# High_Voltage_Converter.net
KiCad netlist of a schematic drawn in Altium Designer
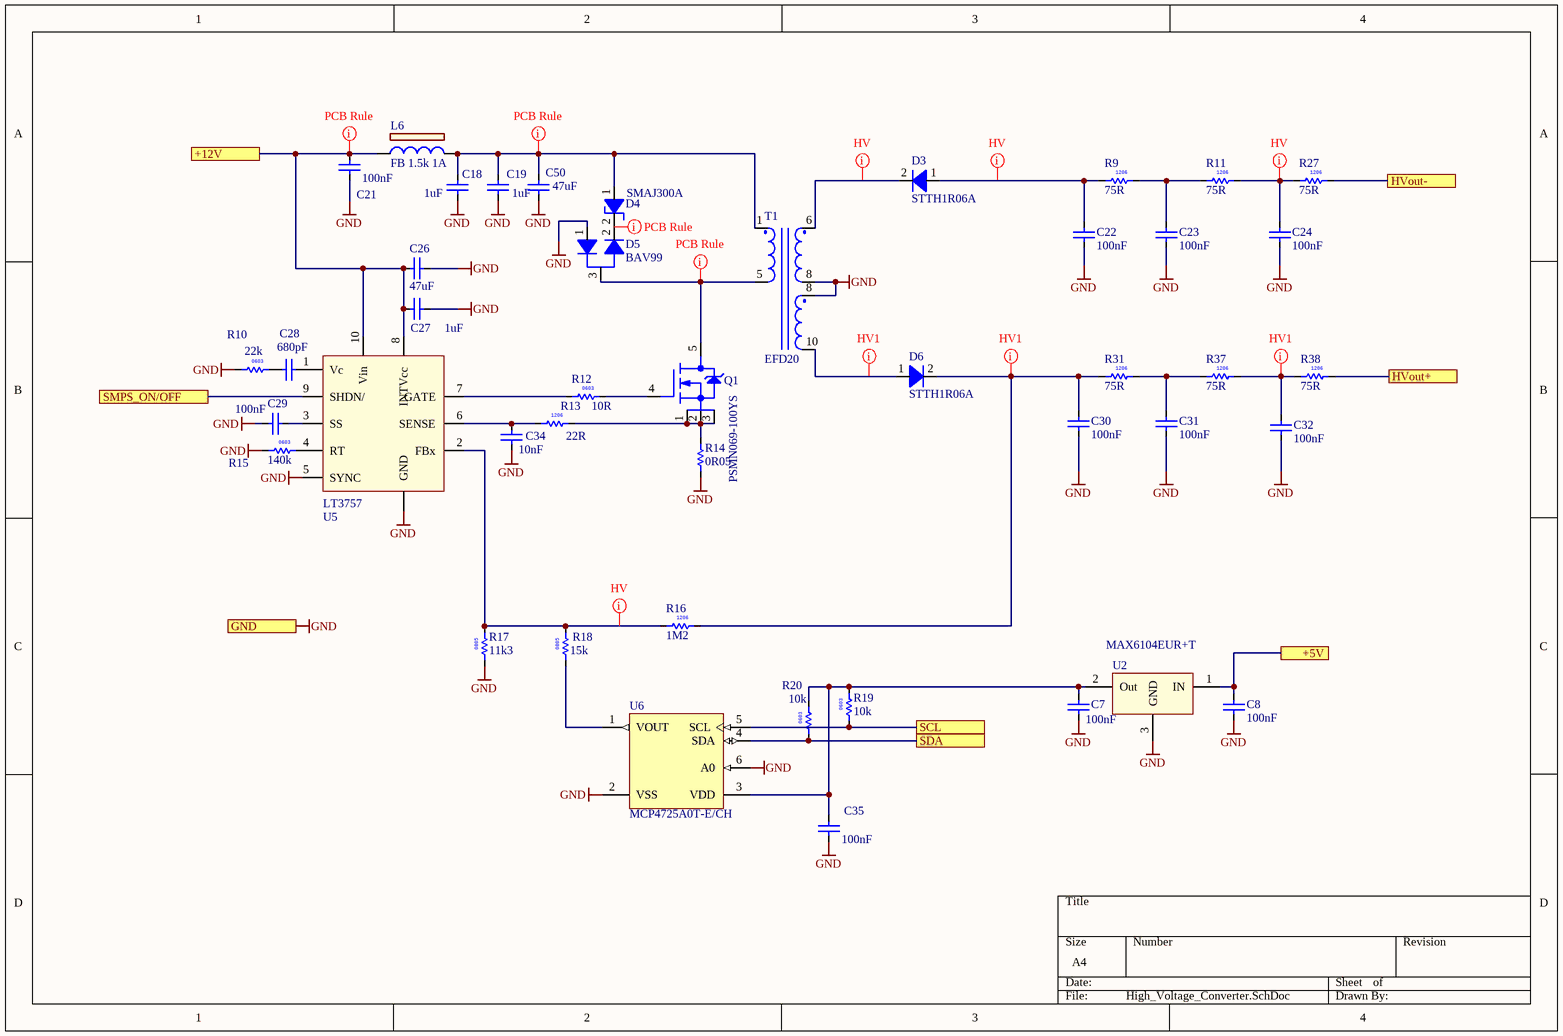
[diagram p0: High_Voltage_Converter.SchDoc]

(export (version "E")
  (design (tool "Eeschema 10.0.6"))
  (components
    (comp (ref "C7")
      (value "100nF")
      (footprint "C0603V")
      (description "MLCC, 0.1uF 16V 10% X7R 0603")
      (fields (field (name "PART NUMBER") "C0000005") (field (name "VOLTAGE") "16"))
      (libsource (lib "KTU_DB") (part "C_SM"))
    )
    (comp (ref "C8")
      (value "100nF")
      (footprint "C0603V")
      (description "MLCC, 0.1uF 16V 10% X7R 0603")
      (fields (field (name "PART NUMBER") "C0000005") (field (name "VOLTAGE") "16"))
      (libsource (lib "KTU_DB") (part "C_SM"))
    )
    (comp (ref "C18")
      (value "1uF")
      (footprint "CAPC2012N")
      (description "MLCC, 0805, X5R, 16V, 1UF")
      (fields (field (name "PART NUMBER") "C0000037") (field (name "VOLTAGE") "16"))
      (libsource (lib "KTU_DB") (part "C_SM"))
    )
    (comp (ref "C19")
      (value "1uF")
      (footprint "CAPC2012N")
      (description "MLCC, 0805, X5R, 16V, 1UF")
      (fields (field (name "PART NUMBER") "C0000037") (field (name "VOLTAGE") "16"))
      (libsource (lib "KTU_DB") (part "C_SM"))
    )
    (comp (ref "C21")
      (value "100nF")
      (footprint "C0603V")
      (description "MLCC, 0.1uF 16V 10% X7R 0603")
      (fields (field (name "PART NUMBER") "C0000005") (field (name "VOLTAGE") "16"))
      (libsource (lib "KTU_DB") (part "C_SM"))
    )
    (comp (ref "C22")
      (value "100nF")
      (footprint "C1808")
      (description "MLCC, X7R, 100NF, 630V, 1808")
      (fields (field (name "PART NUMBER") "C0000111") (field (name "VOLTAGE") "630"))
      (libsource (lib "KTU_DB") (part "C_SM"))
    )
    (comp (ref "C23")
      (value "100nF")
      (footprint "C1808")
      (description "MLCC, X7R, 100NF, 630V, 1808")
      (fields (field (name "PART NUMBER") "C0000111") (field (name "VOLTAGE") "630"))
      (libsource (lib "KTU_DB") (part "C_SM"))
    )
    (comp (ref "C24")
      (value "100nF")
      (footprint "C1808")
      (description "MLCC, X7R, 100NF, 630V, 1808")
      (fields (field (name "PART NUMBER") "C0000111") (field (name "VOLTAGE") "630"))
      (libsource (lib "KTU_DB") (part "C_SM"))
    )
    (comp (ref "C26")
      (value "47uF")
      (footprint "CAPC3225N")
      (description "MLCC, 1210, 47uF, 16V")
      (fields (field (name "PART NUMBER") "C0000077") (field (name "VOLTAGE") "16"))
      (libsource (lib "KTU_DB") (part "C_SM"))
    )
    (comp (ref "C27")
      (value "1uF")
      (footprint "CAPC2012N")
      (description "MLCC, 0805, X5R, 16V, 1UF")
      (fields (field (name "PART NUMBER") "C0000037") (field (name "VOLTAGE") "16"))
      (libsource (lib "KTU_DB") (part "C_SM"))
    )
    (comp (ref "C28")
      (value "680pF")
      (footprint "CAPC3216N")
      (description "MLCC, 680PF, 630V, C0G/NP0, 1206")
      (fields (field (name "PART NUMBER") "C0000056") (field (name "VOLTAGE") "630"))
      (libsource (lib "KTU_DB") (part "C_SM"))
    )
    (comp (ref "C29")
      (value "100nF")
      (footprint "C0603V")
      (description "MLCC, 0.1uF 16V 10% X7R 0603")
      (fields (field (name "PART NUMBER") "C0000005") (field (name "VOLTAGE") "16"))
      (libsource (lib "KTU_DB") (part "C_SM"))
    )
    (comp (ref "C30")
      (value "100nF")
      (footprint "C1808")
      (description "MLCC, X7R, 100NF, 630V, 1808")
      (fields (field (name "PART NUMBER") "C0000111") (field (name "VOLTAGE") "630"))
      (libsource (lib "KTU_DB") (part "C_SM"))
    )
    (comp (ref "C31")
      (value "100nF")
      (footprint "C1808")
      (description "MLCC, X7R, 100NF, 630V, 1808")
      (fields (field (name "PART NUMBER") "C0000111") (field (name "VOLTAGE") "630"))
      (libsource (lib "KTU_DB") (part "C_SM"))
    )
    (comp (ref "C32")
      (value "100nF")
      (footprint "C1808")
      (description "MLCC, X7R, 100NF, 630V, 1808")
      (fields (field (name "PART NUMBER") "C0000111") (field (name "VOLTAGE") "630"))
      (libsource (lib "KTU_DB") (part "C_SM"))
    )
    (comp (ref "C34")
      (value "10nF")
      (footprint "CAPC3216N")
      (description "MLCC, 10nF, 630V, ±10% ,X7R, 1206")
      (fields (field (name "PART NUMBER") "C0000012") (field (name "VOLTAGE") "630"))
      (libsource (lib "KTU_DB") (part "C_SM"))
    )
    (comp (ref "C35")
      (value "100nF")
      (footprint "C0603V")
      (description "MLCC, 0.1uF 16V 10% X7R 0603")
      (fields (field (name "PART NUMBER") "C0000005") (field (name "VOLTAGE") "16"))
      (libsource (lib "KTU_DB") (part "C_SM"))
    )
    (comp (ref "C50")
      (value "47uF")
      (footprint "CAPC3225N")
      (description "MLCC, 1210, 47uF, 16V")
      (fields (field (name "PART NUMBER") "C0000077") (field (name "VOLTAGE") "16"))
      (libsource (lib "KTU_DB") (part "C_SM"))
    )
    (comp (ref "D3")
      (value "STTH1R06A")
      (footprint "DO-214AC")
      (description "DIODE, fast, 1A, 600V, SMD, SMA")
      (fields (field (name "PART NUMBER") "D0000024") (field (name "MANUFACTURER") "ST Microelectronics"))
      (libsource (lib "KTU_DB") (part "Diode"))
    )
    (comp (ref "D4")
      (value "SMAJ300A")
      (footprint "DO-214AC")
      (description "TVS DIODE, 400W, 300V, DO-214AC")
      (fields (field (name "PART NUMBER") "D0000021") (field (name "MANUFACTURER") "LITTELFUSE"))
      (libsource (lib "KTU_DB") (part "Diode_transzorb"))
    )
    (comp (ref "D5")
      (value "BAV99")
      (footprint "SOT95P240-3L")
      (description "DIODE SW DUAL 75V 350mW SOT23")
      (fields (field (name "PART NUMBER") "D0000001") (field (name "MANUFACTURER PART NUMBER") "BAV99-7-F"))
      (libsource (lib "KTU_DB") (part "BAV99"))
    )
    (comp (ref "D6")
      (value "STTH1R06A")
      (footprint "DO-214AC")
      (description "DIODE, fast, 1A, 600V, SMD, SMA")
      (fields (field (name "PART NUMBER") "D0000024") (field (name "MANUFACTURER") "ST Microelectronics"))
      (libsource (lib "KTU_DB") (part "Diode"))
    )
    (comp (ref "L6")
      (value "FB 1.5k 1A")
      (footprint "LL0805\\2P")
      (description "BEAD FERRITE, SMD 1500OHM, 0805")
      (fields (field (name "PART NUMBER") "L0000004") (field (name "MANUFACTURER") "Wurth Elektronik"))
      (libsource (lib "KTU_DB") (part "L_core"))
    )
    (comp (ref "Q1")
      (value "PSMN069-100YS")
      (footprint "SOT669")
      (description "MOSFET 100V, 72.4 mOhm standard level, LFPAK")
      (fields (field (name "PART NUMBER") "Q0000050") (field (name "MANUFACTURER") "NXP"))
      (libsource (lib "KTU_DB") (part "MOSFET_N_GDSSS"))
    )
    (comp (ref "R9")
      (value "75R")
      (footprint "RESC3216N")
      (description "75R 5% 1206 1/4W")
      (fields (field (name "TOLERANCE") "±5%") (field (name "POWER") "1/4W"))
      (libsource (lib "KTU_DB") (part "R1206"))
    )
    (comp (ref "R10")
      (value "22k")
      (footprint "RESC1608X50N")
      (description "Res, 22K, 0603 (1608 metric), ±1%, 100mW, 75V")
      (fields (field (name "TOLERANCE") "±1%") (field (name "POWER") "100mW"))
      (libsource (lib "KTU_DB") (part "R0603"))
    )
    (comp (ref "R11")
      (value "75R")
      (footprint "RESC3216N")
      (description "75R 5% 1206 1/4W")
      (fields (field (name "TOLERANCE") "±5%") (field (name "POWER") "1/4W"))
      (libsource (lib "KTU_DB") (part "R1206"))
    )
    (comp (ref "R12")
      (value "10R")
      (footprint "RESC1608N")
      (description "Res, 0603 0.1W 5%")
      (fields (field (name "TOLERANCE") "±5%") (field (name "POWER") "0.1W"))
      (libsource (lib "KTU_DB") (part "R0603"))
    )
    (comp (ref "R13")
      (value "22R")
      (footprint "RESC3216N")
      (description "22R 5% 1206 1/4W")
      (fields (field (name "TOLERANCE") "±5%") (field (name "POWER") "1/4W"))
      (libsource (lib "KTU_DB") (part "R1206"))
    )
    (comp (ref "R14")
      (value "0R05")
      (footprint "RESC6432AN")
      (description "Res, 0.05R 1% 2512 1W")
      (fields (field (name "TOLERANCE") "±1%") (field (name "POWER") "1W"))
      (libsource (lib "KTU_DB") (part "Res"))
    )
    (comp (ref "R15")
      (value "140k")
      (footprint "RESC1608X50N")
      (description "Res, 140K, 0603 (1608 metric), ±1%, 100mW, 75V")
      (fields (field (name "TOLERANCE") "±1%") (field (name "POWER") "100mW"))
      (libsource (lib "KTU_DB") (part "R0603"))
    )
    (comp (ref "R16")
      (value "1M2")
      (footprint "RESC3216N")
      (description "Res, 1M 0.25W, 1% 1206")
      (fields (field (name "TOLERANCE") "±1%") (field (name "POWER") "0.25W"))
      (libsource (lib "KTU_DB") (part "R1206"))
    )
    (comp (ref "R17")
      (value "11k3")
      (footprint "RESC2012N")
      (description "Res, 11K 5% 0805 1/8W")
      (fields (field (name "TOLERANCE") "±5%") (field (name "POWER") "1/8W"))
      (libsource (lib "KTU_DB") (part "R0805"))
    )
    (comp (ref "R18")
      (value "15k")
      (footprint "RESC2012N")
      (description "Res, 11K 5% 0805 1/8W")
      (fields (field (name "TOLERANCE") "±5%") (field (name "POWER") "1/8W"))
      (libsource (lib "KTU_DB") (part "R0805"))
    )
    (comp (ref "R19")
      (value "10k")
      (footprint "RESC1608N")
      (description "Res, 10K 0.063W 75V 1%  0603")
      (fields (field (name "TOLERANCE") "±1%") (field (name "POWER") "0.063W"))
      (libsource (lib "KTU_DB") (part "R0603"))
    )
    (comp (ref "R20")
      (value "10k")
      (footprint "RESC1608N")
      (description "Res, 10K 0.063W 75V 1%  0603")
      (fields (field (name "TOLERANCE") "±1%") (field (name "POWER") "0.063W"))
      (libsource (lib "KTU_DB") (part "R0603"))
    )
    (comp (ref "R27")
      (value "75R")
      (footprint "RESC3216N")
      (description "75R 5% 1206 1/4W")
      (fields (field (name "TOLERANCE") "±5%") (field (name "POWER") "1/4W"))
      (libsource (lib "KTU_DB") (part "R1206"))
    )
    (comp (ref "R31")
      (value "75R")
      (footprint "RESC3216N")
      (description "75R 5% 1206 1/4W")
      (fields (field (name "TOLERANCE") "±5%") (field (name "POWER") "1/4W"))
      (libsource (lib "KTU_DB") (part "R1206"))
    )
    (comp (ref "R37")
      (value "75R")
      (footprint "RESC3216N")
      (description "75R 5% 1206 1/4W")
      (fields (field (name "TOLERANCE") "±5%") (field (name "POWER") "1/4W"))
      (libsource (lib "KTU_DB") (part "R1206"))
    )
    (comp (ref "R38")
      (value "75R")
      (footprint "RESC3216N")
      (description "75R 5% 1206 1/4W")
      (fields (field (name "TOLERANCE") "±5%") (field (name "POWER") "1/4W"))
      (libsource (lib "KTU_DB") (part "R1206"))
    )
    (comp (ref "T1")
      (value "EFD20")
      (footprint "EFD_20")
      (description "EFD_20")
      (libsource (lib "D_klase") (part "EFD_20"))
    )
    (comp (ref "U2")
      (value "MAX6104EUR+T")
      (footprint "SOT23-3")
      (description "Low-Cost, Micropower, Low-Dropout,  High-Output-Current, SOT23 Voltage References")
      (libsource (lib "D_klase") (part "MAX6104EUR+T"))
    )
    (comp (ref "U5")
      (value "LT3757")
      (footprint "10-LEAD PLASTIC MSOP - duplicate")
      (description "Boost, Flyback, SEPIC and  Inverting Controller")
      (libsource (lib "D_klase") (part "LT3757"))
    )
    (comp (ref "U6")
      (value "MCP4725A0T-E/CH")
      (footprint "SOT-23-CH6_N")
      (fields (field (name "PUBLISHER") "Altium Limited"))
      (libsource (lib "Microchip Mixed Signal") (part "MCP4725A0T-E/CH"))
    )
  )
  (nets
    (net (code "1") (name "/+5V") (class "Default")
      (node (ref "C8") (pin "2") (pinfunction "2_2") (pintype "passive"))
      (node (ref "U2") (pin "1") (pinfunction "IN_1") (pintype "passive"))
    )
    (net (code "2") (name "/+12V") (class "Default")
      (node (ref "C21") (pin "2") (pinfunction "2_2") (pintype "passive"))
      (node (ref "C26") (pin "1") (pinfunction "1_1") (pintype "passive"))
      (node (ref "C27") (pin "1") (pinfunction "1_1") (pintype "passive"))
      (node (ref "L6") (pin "1") (pinfunction "1_1") (pintype "passive"))
      (node (ref "U5") (pin "10") (pinfunction "Vin_10") (pintype "passive"))
      (node (ref "U5") (pin "8") (pinfunction "INTVcc_8") (pintype "passive"))
    )
    (net (code "3") (name "/HVout+") (class "Default")
      (node (ref "R38") (pin "2") (pinfunction "2_2") (pintype "passive"))
    )
    (net (code "4") (name "/HVout-") (class "Default")
      (node (ref "R27") (pin "2") (pinfunction "2_2") (pintype "passive"))
    )
    (net (code "5") (name "/SCL") (class "Default")
      (node (ref "R19") (pin "1") (pinfunction "1_1") (pintype "passive"))
      (node (ref "U6") (pin "5") (pinfunction "SCL_5") (pintype "input"))
    )
    (net (code "6") (name "/SDA") (class "Default")
      (node (ref "R20") (pin "1") (pinfunction "1_1") (pintype "passive"))
      (node (ref "U6") (pin "4") (pinfunction "SDA_4") (pintype "bidirectional"))
    )
    (net (code "7") (name "/SMPS_ON{slash}OFF") (class "Default")
      (node (ref "U5") (pin "9") (pinfunction "SHDN/_9") (pintype "passive"))
    )
    (net (code "8") (name "GND") (class "Default")
      (node (ref "C18") (pin "2") (pinfunction "2_2") (pintype "passive"))
      (node (ref "C19") (pin "2") (pinfunction "2_2") (pintype "passive"))
      (node (ref "C21") (pin "1") (pinfunction "1_1") (pintype "passive"))
      (node (ref "C22") (pin "1") (pinfunction "1_1") (pintype "passive"))
      (node (ref "C23") (pin "1") (pinfunction "1_1") (pintype "passive"))
      (node (ref "C24") (pin "1") (pinfunction "1_1") (pintype "passive"))
      (node (ref "C26") (pin "2") (pinfunction "2_2") (pintype "passive"))
      (node (ref "C27") (pin "2") (pinfunction "2_2") (pintype "passive"))
      (node (ref "C29") (pin "2") (pinfunction "2_2") (pintype "passive"))
      (node (ref "C30") (pin "1") (pinfunction "1_1") (pintype "passive"))
      (node (ref "C31") (pin "1") (pinfunction "1_1") (pintype "passive"))
      (node (ref "C32") (pin "1") (pinfunction "1_1") (pintype "passive"))
      (node (ref "C34") (pin "1") (pinfunction "1_1") (pintype "passive"))
      (node (ref "C35") (pin "1") (pinfunction "1_1") (pintype "passive"))
      (node (ref "C50") (pin "1") (pinfunction "1_1") (pintype "passive"))
      (node (ref "C7") (pin "1") (pinfunction "1_1") (pintype "passive"))
      (node (ref "C8") (pin "1") (pinfunction "1_1") (pintype "passive"))
      (node (ref "D5") (pin "1") (pinfunction "A1_1") (pintype "passive"))
      (node (ref "R10") (pin "1") (pinfunction "1_1") (pintype "passive"))
      (node (ref "R14") (pin "1") (pinfunction "1_1") (pintype "passive"))
      (node (ref "R15") (pin "1") (pinfunction "1_1") (pintype "passive"))
      (node (ref "R17") (pin "1") (pinfunction "1_1") (pintype "passive"))
      (node (ref "T1") (pin "8") (pinfunction "8_8") (pintype "passive"))
      (node (ref "U2") (pin "3") (pinfunction "GND_3") (pintype "passive"))
      (node (ref "U5") (pin "5") (pinfunction "SYNC_5") (pintype "passive"))
      (node (ref "U5") (pin "GND") (pinfunction "GND_GND") (pintype "passive"))
      (node (ref "U6") (pin "2") (pinfunction "VSS_2") (pintype "power_in"))
      (node (ref "U6") (pin "6") (pinfunction "A0_6") (pintype "input"))
    )
    (net (code "9") (name "Net-(C23-Pad2)") (class "Default")
      (node (ref "C23") (pin "2") (pinfunction "2_2") (pintype "passive"))
      (node (ref "R11") (pin "1") (pinfunction "1_1") (pintype "passive"))
      (node (ref "R9") (pin "2") (pinfunction "2_2") (pintype "passive"))
    )
    (net (code "10") (name "Net-(C24-Pad2)") (class "Default")
      (node (ref "C24") (pin "2") (pinfunction "2_2") (pintype "passive"))
      (node (ref "R11") (pin "2") (pinfunction "2_2") (pintype "passive"))
      (node (ref "R27") (pin "1") (pinfunction "1_1") (pintype "passive"))
    )
    (net (code "11") (name "Net-(C28-Pad1)") (class "Default")
      (node (ref "C28") (pin "1") (pinfunction "1_1") (pintype "passive"))
      (node (ref "R10") (pin "2") (pinfunction "2_2") (pintype "passive"))
    )
    (net (code "12") (name "Net-(C31-Pad2)") (class "Default")
      (node (ref "C31") (pin "2") (pinfunction "2_2") (pintype "passive"))
      (node (ref "R31") (pin "2") (pinfunction "2_2") (pintype "passive"))
      (node (ref "R37") (pin "1") (pinfunction "1_1") (pintype "passive"))
    )
    (net (code "13") (name "Net-(C32-Pad2)") (class "Default")
      (node (ref "C32") (pin "2") (pinfunction "2_2") (pintype "passive"))
      (node (ref "R37") (pin "2") (pinfunction "2_2") (pintype "passive"))
      (node (ref "R38") (pin "1") (pinfunction "1_1") (pintype "passive"))
    )
    (net (code "14") (name "Net-(D3-anode)") (class "Default")
      (node (ref "C22") (pin "2") (pinfunction "2_2") (pintype "passive"))
      (node (ref "D3") (pin "1") (pinfunction "anode_1") (pintype "passive"))
      (node (ref "R9") (pin "1") (pinfunction "1_1") (pintype "passive"))
    )
    (net (code "15") (name "Net-(D3-cathode)") (class "Default")
      (node (ref "D3") (pin "2") (pinfunction "cathode_2") (pintype "passive"))
      (node (ref "T1") (pin "6") (pinfunction "6_6") (pintype "passive"))
    )
    (net (code "16") (name "Net-(D4-ANODE)") (class "Default")
      (node (ref "C18") (pin "1") (pinfunction "1_1") (pintype "passive"))
      (node (ref "C19") (pin "1") (pinfunction "1_1") (pintype "passive"))
      (node (ref "C50") (pin "2") (pinfunction "2_2") (pintype "passive"))
      (node (ref "D4") (pin "1") (pinfunction "ANODE_1") (pintype "passive"))
      (node (ref "L6") (pin "2") (pinfunction "2_2") (pintype "passive"))
      (node (ref "T1") (pin "1") (pinfunction "1_1") (pintype "passive"))
    )
    (net (code "17") (name "Net-(D4-CATHODE)") (class "Default")
      (node (ref "D4") (pin "2") (pinfunction "CATHODE_2") (pintype "passive"))
      (node (ref "D5") (pin "2") (pinfunction "A_2") (pintype "passive"))
    )
    (net (code "18") (name "Net-(D5-K)") (class "Default")
      (node (ref "D5") (pin "3") (pinfunction "K_3") (pintype "passive"))
      (node (ref "Q1") (pin "5") (pinfunction "D_5") (pintype "passive"))
      (node (ref "T1") (pin "5") (pinfunction "5_5") (pintype "passive"))
    )
    (net (code "19") (name "Net-(D6-anode)") (class "Default")
      (node (ref "D6") (pin "1") (pinfunction "anode_1") (pintype "passive"))
      (node (ref "T1") (pin "10") (pinfunction "10_10") (pintype "passive"))
    )
    (net (code "20") (name "Net-(D6-cathode)") (class "Default")
      (node (ref "C30") (pin "2") (pinfunction "2_2") (pintype "passive"))
      (node (ref "D6") (pin "2") (pinfunction "cathode_2") (pintype "passive"))
      (node (ref "R16") (pin "2") (pinfunction "2_2") (pintype "passive"))
      (node (ref "R31") (pin "1") (pinfunction "1_1") (pintype "passive"))
    )
    (net (code "21") (name "Net-(Q1-G)") (class "Default")
      (node (ref "Q1") (pin "4") (pinfunction "G_4") (pintype "passive"))
      (node (ref "R12") (pin "2") (pinfunction "2_2") (pintype "passive"))
    )
    (net (code "22") (name "Net-(Q1-S-Pad1)") (class "Default")
      (node (ref "Q1") (pin "1") (pinfunction "S_1") (pintype "passive"))
      (node (ref "Q1") (pin "2") (pinfunction "S_2") (pintype "passive"))
      (node (ref "Q1") (pin "3") (pinfunction "S_3") (pintype "passive"))
      (node (ref "R13") (pin "2") (pinfunction "2_2") (pintype "passive"))
      (node (ref "R14") (pin "2") (pinfunction "2_2") (pintype "passive"))
    )
    (net (code "23") (name "Net-(U2-Out)") (class "Default")
      (node (ref "C35") (pin "2") (pinfunction "2_2") (pintype "passive"))
      (node (ref "C7") (pin "2") (pinfunction "2_2") (pintype "passive"))
      (node (ref "R19") (pin "2") (pinfunction "2_2") (pintype "passive"))
      (node (ref "R20") (pin "2") (pinfunction "2_2") (pintype "passive"))
      (node (ref "U2") (pin "2") (pinfunction "Out_2") (pintype "passive"))
      (node (ref "U6") (pin "3") (pinfunction "VDD_3") (pintype "power_in"))
    )
    (net (code "24") (name "Net-(U5-FBx)") (class "Default")
      (node (ref "R16") (pin "1") (pinfunction "1_1") (pintype "passive"))
      (node (ref "R17") (pin "2") (pinfunction "2_2") (pintype "passive"))
      (node (ref "R18") (pin "2") (pinfunction "2_2") (pintype "passive"))
      (node (ref "U5") (pin "2") (pinfunction "FBx_2") (pintype "passive"))
    )
    (net (code "25") (name "Net-(U5-GATE)") (class "Default")
      (node (ref "R12") (pin "1") (pinfunction "1_1") (pintype "passive"))
      (node (ref "U5") (pin "7") (pinfunction "GATE_7") (pintype "passive"))
    )
    (net (code "26") (name "Net-(U5-RT)") (class "Default")
      (node (ref "R15") (pin "2") (pinfunction "2_2") (pintype "passive"))
      (node (ref "U5") (pin "4") (pinfunction "RT_4") (pintype "passive"))
    )
    (net (code "27") (name "Net-(U5-SENSE)") (class "Default")
      (node (ref "C34") (pin "2") (pinfunction "2_2") (pintype "passive"))
      (node (ref "R13") (pin "1") (pinfunction "1_1") (pintype "passive"))
      (node (ref "U5") (pin "6") (pinfunction "SENSE_6") (pintype "passive"))
    )
    (net (code "28") (name "Net-(U5-SS)") (class "Default")
      (node (ref "C29") (pin "1") (pinfunction "1_1") (pintype "passive"))
      (node (ref "U5") (pin "3") (pinfunction "SS_3") (pintype "passive"))
    )
    (net (code "29") (name "Net-(U5-Vc)") (class "Default")
      (node (ref "C28") (pin "2") (pinfunction "2_2") (pintype "passive"))
      (node (ref "U5") (pin "1") (pinfunction "Vc_1") (pintype "passive"))
    )
    (net (code "30") (name "Net-(U6-VOUT)") (class "Default")
      (node (ref "R18") (pin "1") (pinfunction "1_1") (pintype "passive"))
      (node (ref "U6") (pin "1") (pinfunction "VOUT_1") (pintype "output"))
    )
  )
)
